# 1-Schematic_servo-power.net
KiCad netlist of a schematic drawn in EasyEDA
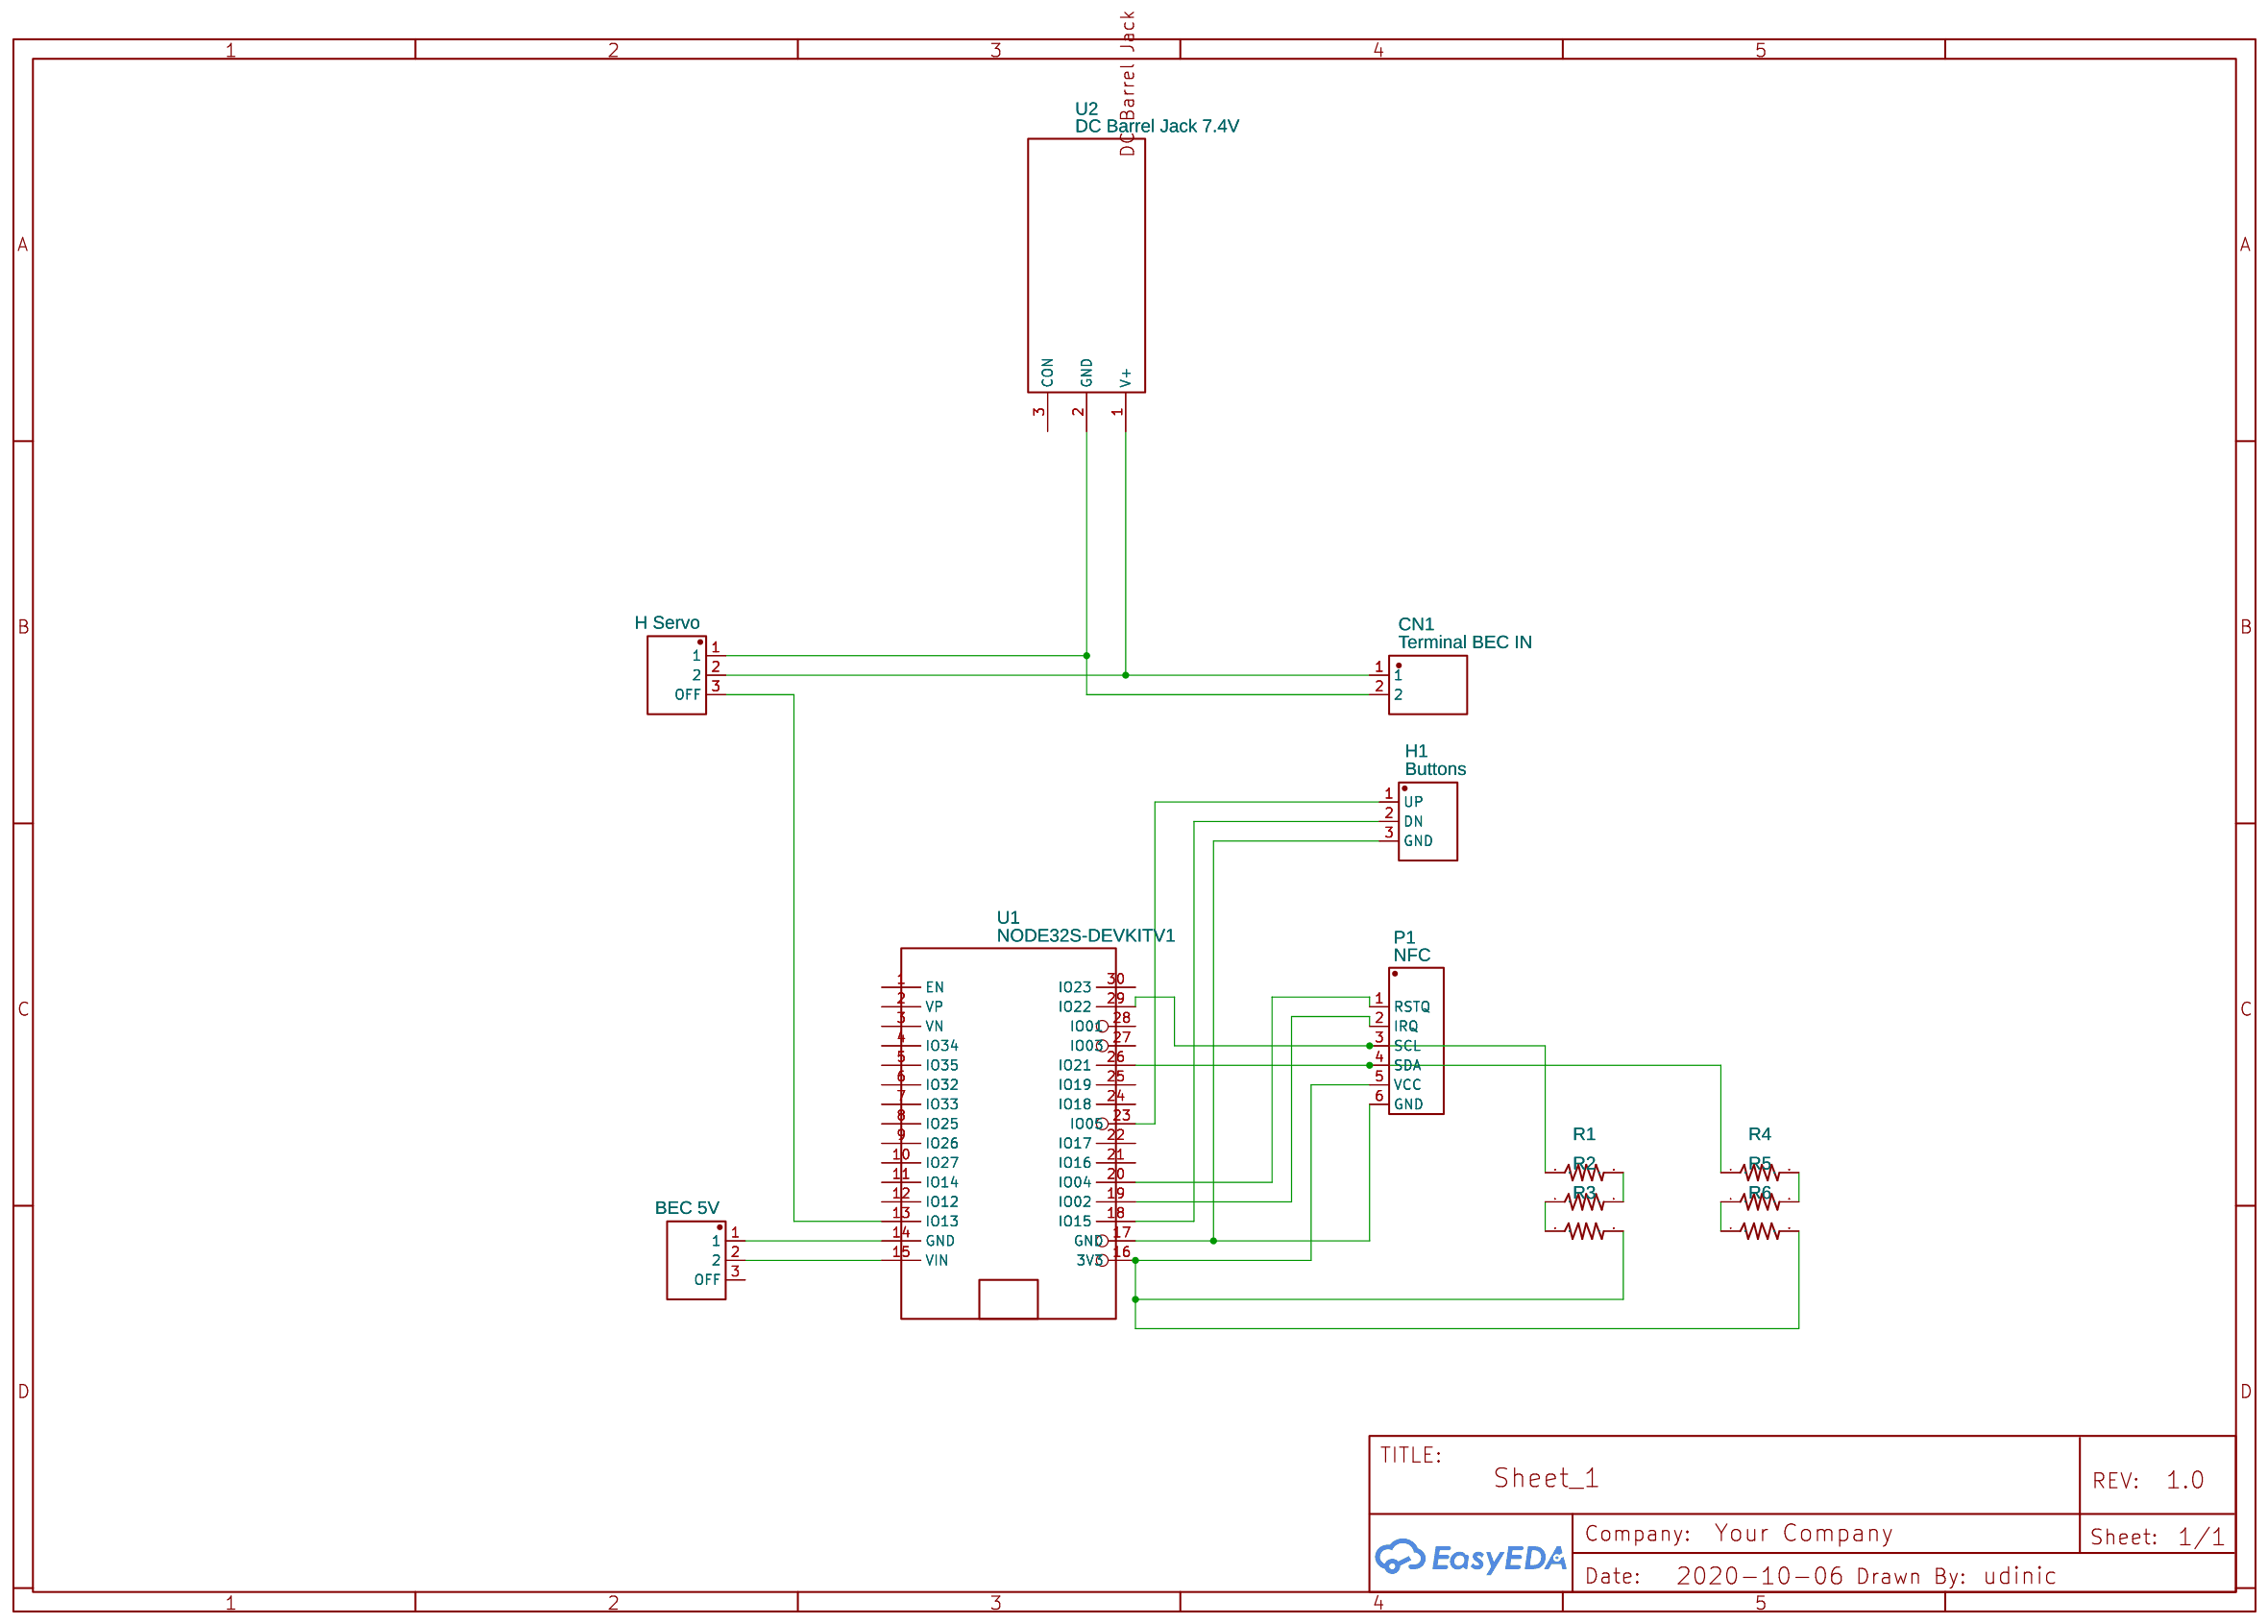
[diagram p0: schematic sheet]

(export (version "E")
  (design (tool "Eeschema 10.0.6"))
  (components
    (comp (ref "CN1")
      (value "Terminal BEC IN")
      (fields (field (name "BOM_Supplier Part") "C146113"))
      (libsource (lib "") (part "Terminal"))
    )
    (comp (ref "H1")
      (value "Buttons")
      (fields
        (field (name "BOM_Manufacturer Part") "Headers  Pins2.54")
        (field (name "BOM_Supplier Part") "C53043")
      )
      (libsource (lib "") (part "HEADERS  PINS2.54 3PINS COPY"))
    )
    (comp (ref "H2")
      (value "H Servo")
      (fields
        (field (name "BOM_Manufacturer Part") "Headers  Pins2.54")
        (field (name "BOM_Supplier Part") "C53043")
      )
      (libsource (lib "") (part "HEADERS  PINS2.54 3PINS"))
    )
    (comp (ref "H3")
      (value "BEC 5V")
      (fields
        (field (name "BOM_Manufacturer Part") "Headers  Pins2.54")
        (field (name "BOM_Supplier Part") "C53043")
      )
      (libsource (lib "") (part "HEADERS  PINS2.54 3PINS"))
    )
    (comp (ref "P1")
      (value "NFC")
      (fields
        (field (name "BOM_Manufacturer Part") "Headers  Pins2.54")
        (field (name "BOM_Supplier Part") "C53043")
      )
      (libsource (lib "") (part "Headers_Pins2.54_1x6"))
    )
    (comp (ref "R1") (value "RESISTOR") (libsource (lib "") (part "RESISTOR")))
    (comp (ref "R2") (value "RESISTOR") (libsource (lib "") (part "RESISTOR")))
    (comp (ref "R3") (value "RESISTOR") (libsource (lib "") (part "RESISTOR")))
    (comp (ref "R4") (value "RESISTOR") (libsource (lib "") (part "RESISTOR")))
    (comp (ref "R5") (value "RESISTOR") (libsource (lib "") (part "RESISTOR")))
    (comp (ref "R6") (value "RESISTOR") (libsource (lib "") (part "RESISTOR")))
    (comp (ref "U1")
      (value "NODE32S-DEVKITV1")
      (fields (field (name "BOM_Manufacturer Part") "New SchematicLib"))
      (libsource (lib "") (part "NODE32S-DEVKITV1"))
    )
    (comp (ref "U2")
      (value "DC Barrel Jack 7.4V")
      (fields
        (field (name "BOM_Manufacturer Part") "DC Barrel Jack 20V 4A")
        (field (name "BOM_Supplier Part") "10811")
      )
      (libsource (lib "") (part "DC Barrel Jack 20V 4A"))
    )
  )
  (nets
    (net (code "1") (name "Net-(H1-DN)") (class "Default")
      (node (ref "H1") (pin "2") (pinfunction "DN_2") (pintype "unspecified"))
      (node (ref "U1") (pin "18") (pinfunction "IO15_18") (pintype "unspecified"))
    )
    (net (code "2") (name "Net-(H1-GND)") (class "Default")
      (node (ref "H1") (pin "3") (pinfunction "GND_3") (pintype "unspecified"))
      (node (ref "P1") (pin "6") (pinfunction "GND_6") (pintype "unspecified"))
      (node (ref "U1") (pin "17") (pinfunction "GND_17") (pintype "unspecified"))
    )
    (net (code "3") (name "Net-(H1-UP)") (class "Default")
      (node (ref "H1") (pin "1") (pinfunction "UP_1") (pintype "unspecified"))
      (node (ref "U1") (pin "23") (pinfunction "IO05_23") (pintype "unspecified"))
    )
    (net (code "4") (name "Net-(H2-OFF)") (class "Default")
      (node (ref "H2") (pin "3") (pinfunction "OFF_3") (pintype "unspecified"))
      (node (ref "U1") (pin "13") (pinfunction "IO13_13") (pintype "unspecified"))
    )
    (net (code "5") (name "Net-(H3-Pad1)") (class "Default")
      (node (ref "H3") (pin "1") (pinfunction "1_1") (pintype "unspecified"))
      (node (ref "U1") (pin "14") (pinfunction "GND_14") (pintype "unspecified"))
    )
    (net (code "6") (name "Net-(P1-IRQ)") (class "Default")
      (node (ref "P1") (pin "2") (pinfunction "IRQ_2") (pintype "unspecified"))
      (node (ref "U1") (pin "19") (pinfunction "IO02_19") (pintype "unspecified"))
    )
    (net (code "7") (name "Net-(P1-RSTQ)") (class "Default")
      (node (ref "P1") (pin "1") (pinfunction "RSTQ_1") (pintype "unspecified"))
      (node (ref "U1") (pin "20") (pinfunction "IO04_20") (pintype "unspecified"))
    )
    (net (code "8") (name "Net-(P1-SCL)") (class "Default")
      (node (ref "P1") (pin "3") (pinfunction "SCL_3") (pintype "unspecified"))
      (node (ref "R1") (pin "1") (pinfunction "1_1") (pintype "unspecified"))
      (node (ref "U1") (pin "29") (pinfunction "IO22_29") (pintype "bidirectional"))
    )
    (net (code "9") (name "Net-(P1-SDA)") (class "Default")
      (node (ref "P1") (pin "4") (pinfunction "SDA_4") (pintype "unspecified"))
      (node (ref "R4") (pin "1") (pinfunction "1_1") (pintype "unspecified"))
      (node (ref "U1") (pin "26") (pinfunction "IO21_26") (pintype "unspecified"))
    )
    (net (code "10") (name "Net-(P1-VCC)") (class "Default")
      (node (ref "P1") (pin "5") (pinfunction "VCC_5") (pintype "unspecified"))
      (node (ref "R3") (pin "2") (pinfunction "2_2") (pintype "unspecified"))
      (node (ref "R6") (pin "2") (pinfunction "2_2") (pintype "unspecified"))
      (node (ref "U1") (pin "16") (pinfunction "3V3_16") (pintype "unspecified"))
    )
    (net (code "11") (name "Net-(R1-Pad2)") (class "Default")
      (node (ref "R1") (pin "2") (pinfunction "2_2") (pintype "unspecified"))
      (node (ref "R2") (pin "2") (pinfunction "2_2") (pintype "unspecified"))
    )
    (net (code "12") (name "Net-(R2-Pad1)") (class "Default")
      (node (ref "R2") (pin "1") (pinfunction "1_1") (pintype "unspecified"))
      (node (ref "R3") (pin "1") (pinfunction "1_1") (pintype "unspecified"))
    )
    (net (code "13") (name "Net-(R4-Pad2)") (class "Default")
      (node (ref "R4") (pin "2") (pinfunction "2_2") (pintype "unspecified"))
      (node (ref "R5") (pin "2") (pinfunction "2_2") (pintype "unspecified"))
    )
    (net (code "14") (name "Net-(R5-Pad1)") (class "Default")
      (node (ref "R5") (pin "1") (pinfunction "1_1") (pintype "unspecified"))
      (node (ref "R6") (pin "1") (pinfunction "1_1") (pintype "unspecified"))
    )
    (net (code "15") (name "Net-(U1-VIN)") (class "Default")
      (node (ref "H3") (pin "2") (pinfunction "2_2") (pintype "unspecified"))
      (node (ref "U1") (pin "15") (pinfunction "VIN_15") (pintype "unspecified"))
    )
    (net (code "16") (name "Net-(U2-GND)") (class "Default")
      (node (ref "CN1") (pin "2") (pinfunction "2_2") (pintype "unspecified"))
      (node (ref "H2") (pin "1") (pinfunction "1_1") (pintype "unspecified"))
      (node (ref "U2") (pin "2") (pinfunction "GND_2") (pintype "unspecified"))
    )
    (net (code "17") (name "Net-(U2-V+)") (class "Default")
      (node (ref "CN1") (pin "1") (pinfunction "1_1") (pintype "unspecified"))
      (node (ref "H2") (pin "2") (pinfunction "2_2") (pintype "unspecified"))
      (node (ref "U2") (pin "1") (pinfunction "V+_1") (pintype "unspecified"))
    )
    (net (code "18") (name "unconnected-(H3-OFF-Pad3)") (class "Default")
      (node (ref "H3") (pin "3") (pinfunction "OFF_3") (pintype "unspecified"))
    )
    (net (code "19") (name "unconnected-(U1-EN-Pad1)") (class "Default")
      (node (ref "U1") (pin "1") (pinfunction "EN_1") (pintype "unspecified"))
    )
    (net (code "20") (name "unconnected-(U1-IO01-Pad28)") (class "Default")
      (node (ref "U1") (pin "28") (pinfunction "IO01_28") (pintype "unspecified"))
    )
    (net (code "21") (name "unconnected-(U1-IO03-Pad27)") (class "Default")
      (node (ref "U1") (pin "27") (pinfunction "IO03_27") (pintype "unspecified"))
    )
    (net (code "22") (name "unconnected-(U1-IO12-Pad12)") (class "Default")
      (node (ref "U1") (pin "12") (pinfunction "IO12_12") (pintype "unspecified"))
    )
    (net (code "23") (name "unconnected-(U1-IO14-Pad11)") (class "Default")
      (node (ref "U1") (pin "11") (pinfunction "IO14_11") (pintype "unspecified"))
    )
    (net (code "24") (name "unconnected-(U1-IO16-Pad21)") (class "Default")
      (node (ref "U1") (pin "21") (pinfunction "IO16_21") (pintype "unspecified"))
    )
    (net (code "25") (name "unconnected-(U1-IO17-Pad22)") (class "Default")
      (node (ref "U1") (pin "22") (pinfunction "IO17_22") (pintype "unspecified"))
    )
    (net (code "26") (name "unconnected-(U1-IO18-Pad24)") (class "Default")
      (node (ref "U1") (pin "24") (pinfunction "IO18_24") (pintype "unspecified"))
    )
    (net (code "27") (name "unconnected-(U1-IO19-Pad25)") (class "Default")
      (node (ref "U1") (pin "25") (pinfunction "IO19_25") (pintype "unspecified"))
    )
    (net (code "28") (name "unconnected-(U1-IO23-Pad30)") (class "Default")
      (node (ref "U1") (pin "30") (pinfunction "IO23_30") (pintype "bidirectional"))
    )
    (net (code "29") (name "unconnected-(U1-IO25-Pad8)") (class "Default")
      (node (ref "U1") (pin "8") (pinfunction "IO25_8") (pintype "unspecified"))
    )
    (net (code "30") (name "unconnected-(U1-IO26-Pad9)") (class "Default")
      (node (ref "U1") (pin "9") (pinfunction "IO26_9") (pintype "unspecified"))
    )
    (net (code "31") (name "unconnected-(U1-IO27-Pad10)") (class "Default")
      (node (ref "U1") (pin "10") (pinfunction "IO27_10") (pintype "unspecified"))
    )
    (net (code "32") (name "unconnected-(U1-IO32-Pad6)") (class "Default")
      (node (ref "U1") (pin "6") (pinfunction "IO32_6") (pintype "unspecified"))
    )
    (net (code "33") (name "unconnected-(U1-IO33-Pad7)") (class "Default")
      (node (ref "U1") (pin "7") (pinfunction "IO33_7") (pintype "unspecified"))
    )
    (net (code "34") (name "unconnected-(U1-IO34-Pad4)") (class "Default")
      (node (ref "U1") (pin "4") (pinfunction "IO34_4") (pintype "unspecified"))
    )
    (net (code "35") (name "unconnected-(U1-IO35-Pad5)") (class "Default")
      (node (ref "U1") (pin "5") (pinfunction "IO35_5") (pintype "unspecified"))
    )
    (net (code "36") (name "unconnected-(U1-VN-Pad3)") (class "Default")
      (node (ref "U1") (pin "3") (pinfunction "VN_3") (pintype "unspecified"))
    )
    (net (code "37") (name "unconnected-(U1-VP-Pad2)") (class "Default")
      (node (ref "U1") (pin "2") (pinfunction "VP_2") (pintype "unspecified"))
    )
    (net (code "38") (name "unconnected-(U2-CON-Pad3)") (class "Default")
      (node (ref "U2") (pin "3") (pinfunction "CON_3") (pintype "unspecified"))
    )
  )
)
